# battery_buzzer.net
KiCad netlist of a schematic drawn in EAGLE
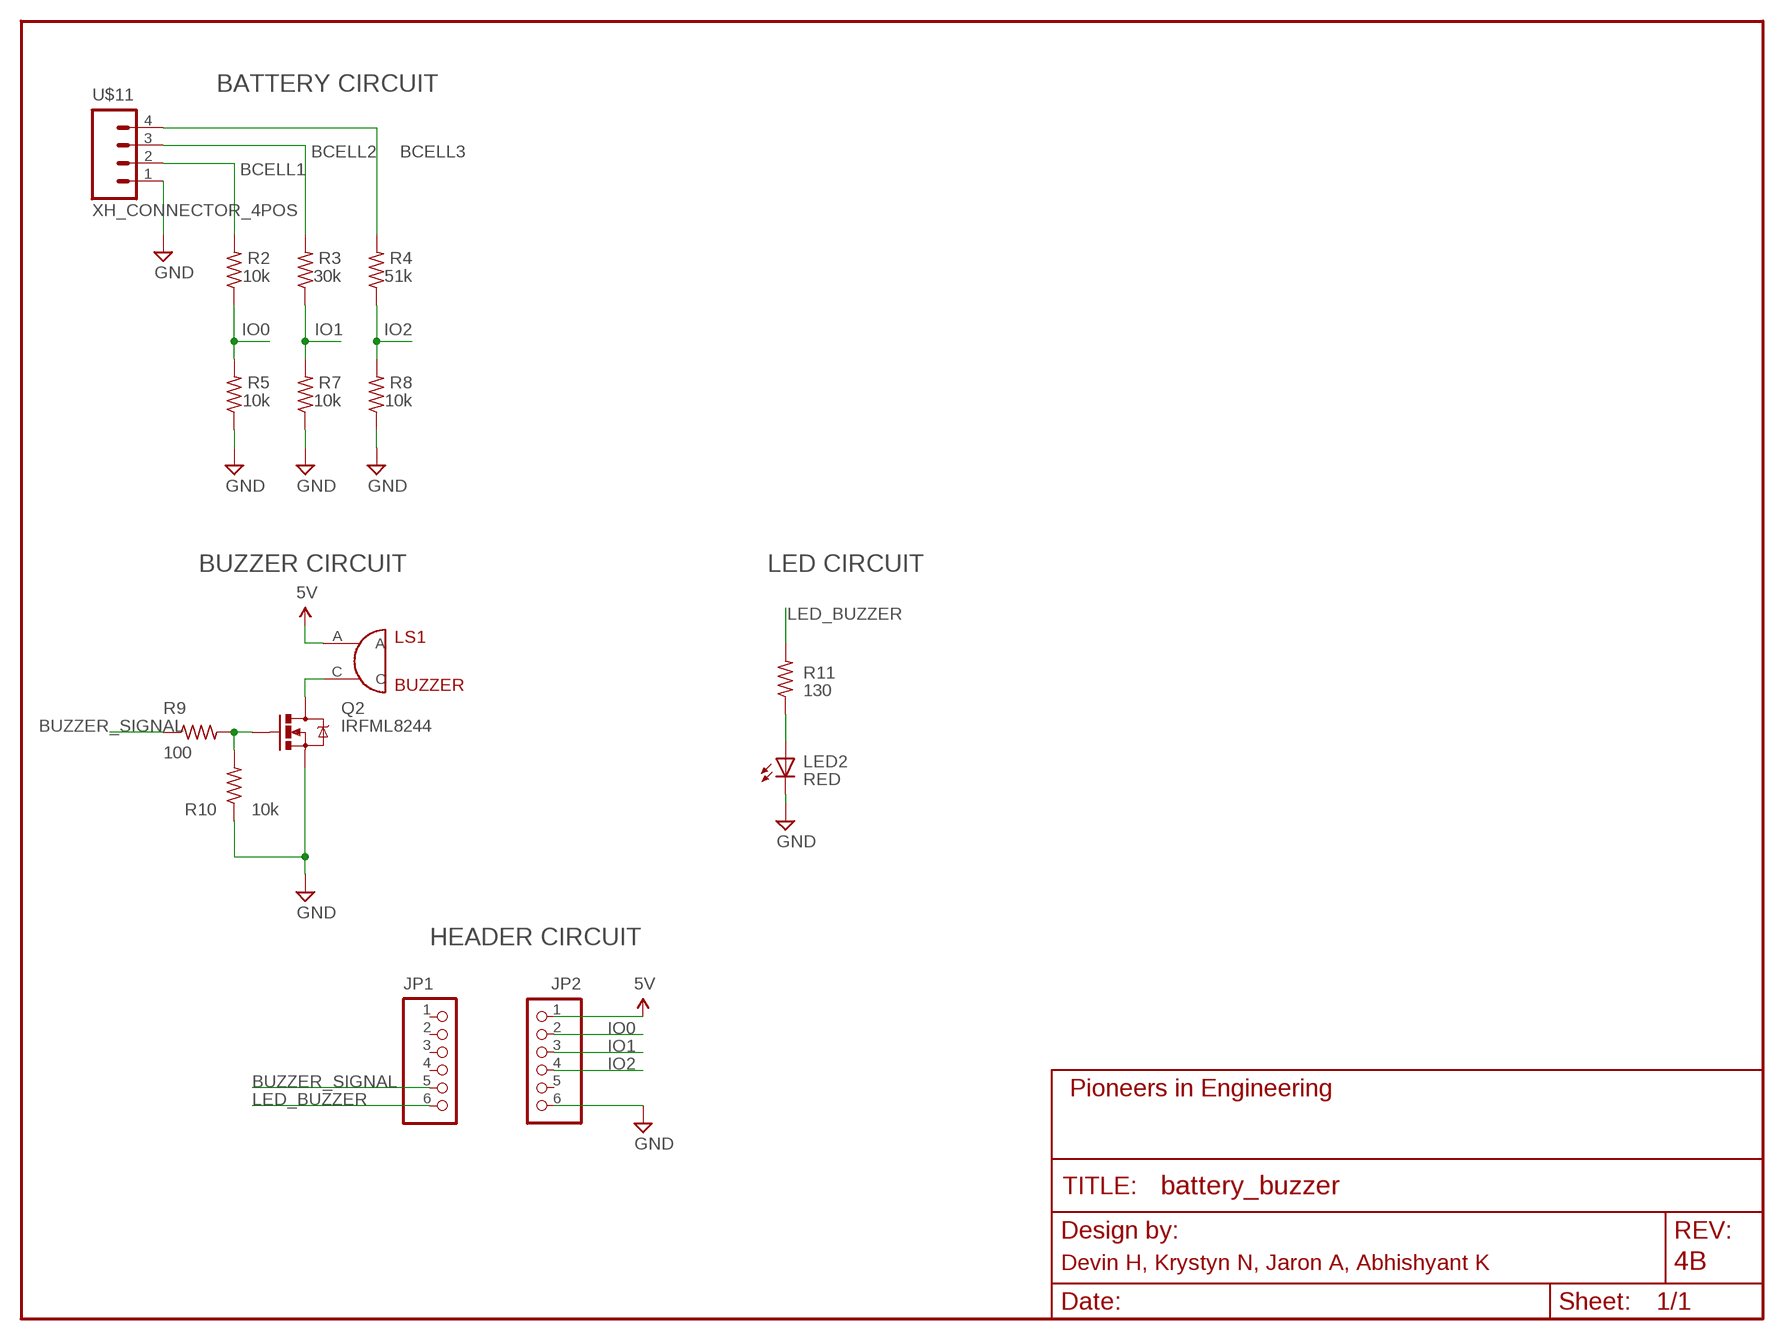
[diagram p0: schematic, sheet 1]

(export (version "E")
  (design (tool "Eeschema 10.0.6"))
  (components
    (comp (ref "JP1")
      (value "PINHD-1X6")
      (footprint "eagle-import:1X06")
      (fields (field (name "PARTNUMBER") "965"))
      (libsource (lib "eagle-import") (part "PINHD-1X6"))
    )
    (comp (ref "JP2")
      (value "PINHD-1X6")
      (footprint "eagle-import:1X06")
      (fields (field (name "PARTNUMBER") "965"))
      (libsource (lib "eagle-import") (part "PINHD-1X6"))
    )
    (comp (ref "LED2")
      (value "RED")
      (footprint "eagle-import:LED-0805")
      (libsource (lib "eagle-import") (part "LED0805"))
    )
    (comp (ref "LS1")
      (value "BUZZER")
      (footprint "eagle-import:BUZZER_MAGNETIC_5V_12MM_RADIAL")
      (libsource (lib "eagle-import") (part "BUZZER"))
    )
    (comp (ref "Q2")
      (value "IRFML8244")
      (footprint "eagle-import:SOT23-3")
      (libsource (lib "eagle-import") (part "MOSFET-NCHANNELSMD"))
    )
    (comp (ref "R2")
      (value "10k")
      (footprint "eagle-import:R0603")
      (libsource (lib "eagle-import") (part "R-US_R0603"))
    )
    (comp (ref "R3")
      (value "30k")
      (footprint "eagle-import:R0603")
      (libsource (lib "eagle-import") (part "R-US_R0603"))
    )
    (comp (ref "R4")
      (value "51k")
      (footprint "eagle-import:R0603")
      (libsource (lib "eagle-import") (part "R-US_R0603"))
    )
    (comp (ref "R5")
      (value "10k")
      (footprint "eagle-import:R0603")
      (libsource (lib "eagle-import") (part "R-US_R0603"))
    )
    (comp (ref "R7")
      (value "10k")
      (footprint "eagle-import:R0603")
      (libsource (lib "eagle-import") (part "R-US_R0603"))
    )
    (comp (ref "R8")
      (value "10k")
      (footprint "eagle-import:R0603")
      (libsource (lib "eagle-import") (part "R-US_R0603"))
    )
    (comp (ref "R9")
      (value "100")
      (footprint "eagle-import:R0603")
      (libsource (lib "eagle-import") (part "R-US_R0603"))
    )
    (comp (ref "R10")
      (value "10k")
      (footprint "eagle-import:R0603")
      (libsource (lib "eagle-import") (part "R-US_R0603"))
    )
    (comp (ref "R11")
      (value "130")
      (footprint "eagle-import:R0603")
      (libsource (lib "eagle-import") (part "R-US_R0603"))
    )
    (comp (ref "U$11")
      (value "XH_CONNECTOR_4POS")
      (footprint "eagle-import:XH_CONNECTOR_4POS_2.5MM")
      (libsource (lib "eagle-import") (part "XH_CONNECTOR_4POS"))
    )
  )
  (nets
    (net (code "1") (name "/BCELL1") (class "Default")
      (node (ref "R2") (pin "2") (pinfunction "2_2") (pintype "passive"))
      (node (ref "U$11") (pin "2") (pinfunction "2_2") (pintype "passive"))
    )
    (net (code "2") (name "/BCELL2") (class "Default")
      (node (ref "R3") (pin "2") (pinfunction "2_2") (pintype "passive"))
      (node (ref "U$11") (pin "3") (pinfunction "3_3") (pintype "passive"))
    )
    (net (code "3") (name "/BCELL3") (class "Default")
      (node (ref "R4") (pin "2") (pinfunction "2_2") (pintype "passive"))
      (node (ref "U$11") (pin "4") (pinfunction "4_4") (pintype "passive"))
    )
    (net (code "4") (name "/BUZZER_SIGNAL") (class "Default")
      (node (ref "JP1") (pin "5") (pinfunction "5_5") (pintype "passive"))
      (node (ref "R9") (pin "1") (pinfunction "1_1") (pintype "passive"))
    )
    (net (code "5") (name "/IO0") (class "Default")
      (node (ref "JP2") (pin "2") (pinfunction "2_2") (pintype "passive"))
      (node (ref "R2") (pin "1") (pinfunction "1_1") (pintype "passive"))
      (node (ref "R5") (pin "2") (pinfunction "2_2") (pintype "passive"))
    )
    (net (code "6") (name "/IO1") (class "Default")
      (node (ref "JP2") (pin "3") (pinfunction "3_3") (pintype "passive"))
      (node (ref "R3") (pin "1") (pinfunction "1_1") (pintype "passive"))
      (node (ref "R7") (pin "2") (pinfunction "2_2") (pintype "passive"))
    )
    (net (code "7") (name "/IO2") (class "Default")
      (node (ref "JP2") (pin "4") (pinfunction "4_4") (pintype "passive"))
      (node (ref "R4") (pin "1") (pinfunction "1_1") (pintype "passive"))
      (node (ref "R8") (pin "2") (pinfunction "2_2") (pintype "passive"))
    )
    (net (code "8") (name "/LED_BUZZER") (class "Default")
      (node (ref "JP1") (pin "6") (pinfunction "6_6") (pintype "passive"))
      (node (ref "R11") (pin "2") (pinfunction "2_2") (pintype "passive"))
    )
    (net (code "9") (name "5V") (class "Default")
      (node (ref "JP2") (pin "1") (pinfunction "1_1") (pintype "passive"))
      (node (ref "LS1") (pin "A") (pinfunction "A_A") (pintype "bidirectional"))
    )
    (net (code "10") (name "GND") (class "Default")
      (node (ref "JP2") (pin "6") (pinfunction "6_6") (pintype "passive"))
      (node (ref "LED2") (pin "C") (pinfunction "C_C") (pintype "passive"))
      (node (ref "Q2") (pin "2") (pinfunction "S_2") (pintype "passive"))
      (node (ref "R10") (pin "1") (pinfunction "1_1") (pintype "passive"))
      (node (ref "R5") (pin "1") (pinfunction "1_1") (pintype "passive"))
      (node (ref "R7") (pin "1") (pinfunction "1_1") (pintype "passive"))
      (node (ref "R8") (pin "1") (pinfunction "1_1") (pintype "passive"))
      (node (ref "U$11") (pin "1") (pinfunction "1_1") (pintype "passive"))
    )
    (net (code "11") (name "Net-(LED2-PadA)") (class "Default")
      (node (ref "LED2") (pin "A") (pinfunction "A_A") (pintype "passive"))
      (node (ref "R11") (pin "1") (pinfunction "1_1") (pintype "passive"))
    )
    (net (code "12") (name "Net-(Q2-D)") (class "Default")
      (node (ref "LS1") (pin "C") (pinfunction "C_C") (pintype "bidirectional"))
      (node (ref "Q2") (pin "3") (pinfunction "D_3") (pintype "passive"))
    )
    (net (code "13") (name "Net-(Q2-G)") (class "Default")
      (node (ref "Q2") (pin "1") (pinfunction "G_1") (pintype "passive"))
      (node (ref "R10") (pin "2") (pinfunction "2_2") (pintype "passive"))
      (node (ref "R9") (pin "2") (pinfunction "2_2") (pintype "passive"))
    )
    (net (code "14") (name "unconnected-(JP1-Pad1)") (class "Default")
      (node (ref "JP1") (pin "1") (pinfunction "1_1") (pintype "passive"))
    )
    (net (code "15") (name "unconnected-(JP1-Pad2)") (class "Default")
      (node (ref "JP1") (pin "2") (pinfunction "2_2") (pintype "passive"))
    )
    (net (code "16") (name "unconnected-(JP1-Pad3)") (class "Default")
      (node (ref "JP1") (pin "3") (pinfunction "3_3") (pintype "passive"))
    )
    (net (code "17") (name "unconnected-(JP1-Pad4)") (class "Default")
      (node (ref "JP1") (pin "4") (pinfunction "4_4") (pintype "passive"))
    )
    (net (code "18") (name "unconnected-(JP2-Pad5)") (class "Default")
      (node (ref "JP2") (pin "5") (pinfunction "5_5") (pintype "passive"))
    )
  )
)
